# MY_DEMO_1602.net
KiCad netlist of a schematic drawn in Altium Designer
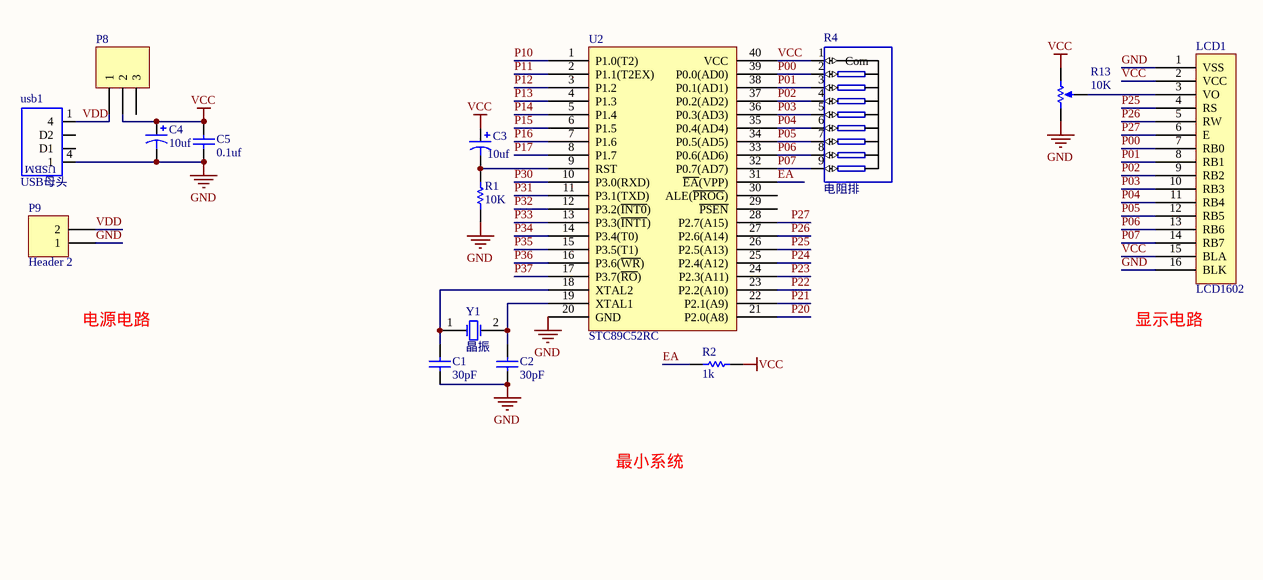
[diagram p0: MY_DEMO_1602.SchDoc]

(export (version "E")
  (design (tool "Eeschema 10.0.6"))
  (components
    (comp (ref "C1")
      (value "30pF")
      (footprint "RAD-0.1")
      (description "Capacitor")
      (fields (field (name "Comment") "瓷片电容") (field (name "PUBLISHER") "Altium Limited"))
      (libsource (lib "Miscellaneous Devices") (part "Cap"))
    )
    (comp (ref "C2")
      (value "30pF")
      (footprint "RAD-0.1")
      (description "Capacitor")
      (fields (field (name "Comment") "瓷片电容") (field (name "PUBLISHER") "Altium Limited"))
      (libsource (lib "Miscellaneous Devices") (part "Cap"))
    )
    (comp (ref "C3")
      (value "10uf")
      (footprint "10UF")
      (description "Polarized Capacitor (Radial)")
      (fields (field (name "Comment") "电解电容") (field (name "PUBLISHER") "Altium Limited"))
      (libsource (lib "Miscellaneous Devices") (part "Cap Pol1"))
    )
    (comp (ref "C4")
      (value "10uf")
      (footprint "10UF")
      (description "Polarized Capacitor (Radial)")
      (fields (field (name "Comment") "点解电容") (field (name "PUBLISHER") "Altium Limited"))
      (libsource (lib "Miscellaneous Devices") (part "Cap Pol1"))
    )
    (comp (ref "C5")
      (value "0.1uf")
      (footprint "CB1")
      (description "Capacitor")
      (fields (field (name "Comment") "瓷片电容") (field (name "PUBLISHER") "Altium Limited"))
      (libsource (lib "Miscellaneous Devices") (part "Cap"))
    )
    (comp (ref "LCD1") (value "LCD1602") (footprint "1602LCD") (libsource (lib "液晶") (part "LCD1602")))
    (comp (ref "P8")
      (value "Header 3")
      (footprint "HDR1X3")
      (description "Header, 3-Pin")
      (fields (field (name "PUBLISHER") "Altium Limited"))
      (libsource (lib "Miscellaneous Connectors") (part "Header 3"))
    )
    (comp (ref "P9")
      (value "Header 2")
      (footprint "HDR1X2")
      (description "Header, 2-Pin")
      (fields (field (name "PUBLISHER") "Altium Limited"))
      (libsource (lib "Miscellaneous Connectors") (part "Header 2"))
    )
    (comp (ref "R1")
      (value "10K")
      (footprint "电阻0.7-1.6")
      (description "Resistor")
      (fields (field (name "Comment") "电阻") (field (name "PUBLISHER") "Altium Limited"))
      (libsource (lib "Miscellaneous Devices") (part "Res1"))
    )
    (comp (ref "R2")
      (value "1k")
      (footprint "电阻0.7-1.6")
      (description "Resistor")
      (fields (field (name "Comment") "电阻") (field (name "PUBLISHER") "Altium Limited"))
      (libsource (lib "Miscellaneous Devices") (part "Res1"))
    )
    (comp (ref "R4") (value "电阻排") (footprint "插槽P9") (libsource (lib "电阻") (part "RES10")))
    (comp (ref "R13")
      (value "10K")
      (footprint "可调电阻5mm")
      (description "Potentiometer")
      (fields (field (name "Comment") "电位器RPot") (field (name "PUBLISHER") "Altium Limited"))
      (libsource (lib "Miscellaneous Devices") (part "RPot"))
    )
    (comp (ref "U2") (value "STC89C52RC") (footprint "DIP-40W") (libsource (lib "51单片机") (part "89C52")))
    (comp (ref "usb1") (value "USB母头") (footprint "A母USB") (libsource (lib "常用2") (part "USB")))
    (comp (ref "Y1")
      (value "晶振")
      (footprint "XTAL")
      (description "Crystal Oscillator")
      (fields (field (name "PUBLISHER") "Altium Limited"))
      (libsource (lib "Miscellaneous Devices") (part "XTAL"))
    )
  )
  (nets
    (net (code "1") (name "/EA") (class "Default")
      (node (ref "R2") (pin "2") (pinfunction "2_2") (pintype "passive"))
      (node (ref "U2") (pin "31") (pinfunction "~{EA}(VPP)_31") (pintype "passive"))
    )
    (net (code "2") (name "/P00") (class "Default")
      (node (ref "LCD1") (pin "7") (pinfunction "RB0_7") (pintype "passive"))
      (node (ref "R4") (pin "2") (pinfunction "2_2") (pintype "bidirectional"))
      (node (ref "U2") (pin "39") (pinfunction "P0.0(AD0)_39") (pintype "passive"))
    )
    (net (code "3") (name "/P01") (class "Default")
      (node (ref "LCD1") (pin "8") (pinfunction "RB1_8") (pintype "passive"))
      (node (ref "R4") (pin "3") (pinfunction "3_3") (pintype "bidirectional"))
      (node (ref "U2") (pin "38") (pinfunction "P0.1(AD1)_38") (pintype "passive"))
    )
    (net (code "4") (name "/P02") (class "Default")
      (node (ref "LCD1") (pin "9") (pinfunction "RB2_9") (pintype "passive"))
      (node (ref "R4") (pin "4") (pinfunction "4_4") (pintype "bidirectional"))
      (node (ref "U2") (pin "37") (pinfunction "P0.2(AD2)_37") (pintype "passive"))
    )
    (net (code "5") (name "/P03") (class "Default")
      (node (ref "LCD1") (pin "10") (pinfunction "RB3_10") (pintype "passive"))
      (node (ref "R4") (pin "5") (pinfunction "5_5") (pintype "bidirectional"))
      (node (ref "U2") (pin "36") (pinfunction "P0.3(AD3)_36") (pintype "passive"))
    )
    (net (code "6") (name "/P04") (class "Default")
      (node (ref "LCD1") (pin "11") (pinfunction "RB4_11") (pintype "passive"))
      (node (ref "R4") (pin "6") (pinfunction "6_6") (pintype "bidirectional"))
      (node (ref "U2") (pin "35") (pinfunction "P0.4(AD4)_35") (pintype "passive"))
    )
    (net (code "7") (name "/P05") (class "Default")
      (node (ref "LCD1") (pin "12") (pinfunction "RB5_12") (pintype "passive"))
      (node (ref "R4") (pin "7") (pinfunction "7_7") (pintype "bidirectional"))
      (node (ref "U2") (pin "34") (pinfunction "P0.5(AD5)_34") (pintype "passive"))
    )
    (net (code "8") (name "/P06") (class "Default")
      (node (ref "LCD1") (pin "13") (pinfunction "RB6_13") (pintype "passive"))
      (node (ref "R4") (pin "8") (pinfunction "8_8") (pintype "bidirectional"))
      (node (ref "U2") (pin "33") (pinfunction "P0.6(AD6)_33") (pintype "passive"))
    )
    (net (code "9") (name "/P07") (class "Default")
      (node (ref "LCD1") (pin "14") (pinfunction "RB7_14") (pintype "passive"))
      (node (ref "R4") (pin "9") (pinfunction "9_9") (pintype "bidirectional"))
      (node (ref "U2") (pin "32") (pinfunction "P0.7(AD7)_32") (pintype "passive"))
    )
    (net (code "10") (name "/P10") (class "Default")
      (node (ref "U2") (pin "1") (pinfunction "P1.0(T2)_1") (pintype "passive"))
    )
    (net (code "11") (name "/P11") (class "Default")
      (node (ref "U2") (pin "2") (pinfunction "P1.1(T2EX)_2") (pintype "passive"))
    )
    (net (code "12") (name "/P12") (class "Default")
      (node (ref "U2") (pin "3") (pinfunction "P1.2_3") (pintype "passive"))
    )
    (net (code "13") (name "/P13") (class "Default")
      (node (ref "U2") (pin "4") (pinfunction "P1.3_4") (pintype "passive"))
    )
    (net (code "14") (name "/P14") (class "Default")
      (node (ref "U2") (pin "5") (pinfunction "P1.4_5") (pintype "passive"))
    )
    (net (code "15") (name "/P15") (class "Default")
      (node (ref "U2") (pin "6") (pinfunction "P1.5_6") (pintype "passive"))
    )
    (net (code "16") (name "/P16") (class "Default")
      (node (ref "U2") (pin "7") (pinfunction "P1.6_7") (pintype "passive"))
    )
    (net (code "17") (name "/P17") (class "Default")
      (node (ref "U2") (pin "8") (pinfunction "P1.7_8") (pintype "passive"))
    )
    (net (code "18") (name "/P20") (class "Default")
      (node (ref "U2") (pin "21") (pinfunction "P2.0(A8)_21") (pintype "passive"))
    )
    (net (code "19") (name "/P21") (class "Default")
      (node (ref "U2") (pin "22") (pinfunction "P2.1(A9)_22") (pintype "passive"))
    )
    (net (code "20") (name "/P22") (class "Default")
      (node (ref "U2") (pin "23") (pinfunction "P2.2(A10)_23") (pintype "passive"))
    )
    (net (code "21") (name "/P23") (class "Default")
      (node (ref "U2") (pin "24") (pinfunction "P2.3(A11)_24") (pintype "passive"))
    )
    (net (code "22") (name "/P24") (class "Default")
      (node (ref "U2") (pin "25") (pinfunction "P2.4(A12)_25") (pintype "passive"))
    )
    (net (code "23") (name "/P25") (class "Default")
      (node (ref "LCD1") (pin "4") (pinfunction "RS_4") (pintype "passive"))
      (node (ref "U2") (pin "26") (pinfunction "P2.5(A13)_26") (pintype "passive"))
    )
    (net (code "24") (name "/P26") (class "Default")
      (node (ref "LCD1") (pin "5") (pinfunction "RW_5") (pintype "passive"))
      (node (ref "U2") (pin "27") (pinfunction "P2.6(A14)_27") (pintype "passive"))
    )
    (net (code "25") (name "/P27") (class "Default")
      (node (ref "LCD1") (pin "6") (pinfunction "E_6") (pintype "passive"))
      (node (ref "U2") (pin "28") (pinfunction "P2.7(A15)_28") (pintype "passive"))
    )
    (net (code "26") (name "/P30") (class "Default")
      (node (ref "U2") (pin "10") (pinfunction "P3.0(RXD)_10") (pintype "passive"))
    )
    (net (code "27") (name "/P31") (class "Default")
      (node (ref "U2") (pin "11") (pinfunction "P3.1(TXD)_11") (pintype "passive"))
    )
    (net (code "28") (name "/P32") (class "Default")
      (node (ref "U2") (pin "12") (pinfunction "P3.2(~{INT0})_12") (pintype "passive"))
    )
    (net (code "29") (name "/P33") (class "Default")
      (node (ref "U2") (pin "13") (pinfunction "P3.3(~{INT1})_13") (pintype "passive"))
    )
    (net (code "30") (name "/P34") (class "Default")
      (node (ref "U2") (pin "14") (pinfunction "P3.4(T0)_14") (pintype "passive"))
    )
    (net (code "31") (name "/P35") (class "Default")
      (node (ref "U2") (pin "15") (pinfunction "P3.5(T1)_15") (pintype "passive"))
    )
    (net (code "32") (name "/P36") (class "Default")
      (node (ref "U2") (pin "16") (pinfunction "P3.6(~{WR})_16") (pintype "passive"))
    )
    (net (code "33") (name "/P37") (class "Default")
      (node (ref "U2") (pin "17") (pinfunction "P3.7(~{RO})_17") (pintype "passive"))
    )
    (net (code "34") (name "/VDD") (class "Default")
      (node (ref "P8") (pin "1") (pinfunction "1_1") (pintype "passive"))
      (node (ref "P9") (pin "2") (pinfunction "2_2") (pintype "passive"))
      (node (ref "usb1") (pin "1") (pinfunction "4_1") (pintype "passive"))
    )
    (net (code "35") (name "GND") (class "Default")
      (node (ref "C1") (pin "1") (pinfunction "1_1") (pintype "passive"))
      (node (ref "C2") (pin "1") (pinfunction "1_1") (pintype "passive"))
      (node (ref "C4") (pin "2") (pinfunction "2_2") (pintype "passive"))
      (node (ref "C5") (pin "1") (pinfunction "1_1") (pintype "passive"))
      (node (ref "LCD1") (pin "1") (pinfunction "VSS_1") (pintype "passive"))
      (node (ref "LCD1") (pin "16") (pinfunction "BLK_16") (pintype "passive"))
      (node (ref "P9") (pin "1") (pinfunction "1_1") (pintype "passive"))
      (node (ref "R1") (pin "1") (pinfunction "1_1") (pintype "passive"))
      (node (ref "R13") (pin "1") (pinfunction "TOP_1") (pintype "passive"))
      (node (ref "U2") (pin "20") (pinfunction "GND_20") (pintype "passive"))
      (node (ref "usb1") (pin "4") (pinfunction "1_4") (pintype "passive"))
    )
    (net (code "36") (name "Net-(LCD1-VO)") (class "Default")
      (node (ref "LCD1") (pin "3") (pinfunction "VO_3") (pintype "passive"))
      (node (ref "R13") (pin "3") (pinfunction "TAP_3") (pintype "passive"))
    )
    (net (code "37") (name "Net-(U2-RST)") (class "Default")
      (node (ref "C3") (pin "2") (pinfunction "2_2") (pintype "passive"))
      (node (ref "R1") (pin "2") (pinfunction "2_2") (pintype "passive"))
      (node (ref "U2") (pin "9") (pinfunction "RST_9") (pintype "passive"))
    )
    (net (code "38") (name "Net-(U2-XTAL1)") (class "Default")
      (node (ref "C2") (pin "2") (pinfunction "2_2") (pintype "passive"))
      (node (ref "U2") (pin "19") (pinfunction "XTAL1_19") (pintype "passive"))
      (node (ref "Y1") (pin "2") (pinfunction "OSC2_2") (pintype "passive"))
    )
    (net (code "39") (name "Net-(U2-XTAL2)") (class "Default")
      (node (ref "C1") (pin "2") (pinfunction "2_2") (pintype "passive"))
      (node (ref "U2") (pin "18") (pinfunction "XTAL2_18") (pintype "passive"))
      (node (ref "Y1") (pin "1") (pinfunction "OSC1_1") (pintype "passive"))
    )
    (net (code "40") (name "VCC") (class "Default")
      (node (ref "C3") (pin "1") (pinfunction "1_1") (pintype "passive"))
      (node (ref "C4") (pin "1") (pinfunction "1_1") (pintype "passive"))
      (node (ref "C5") (pin "2") (pinfunction "2_2") (pintype "passive"))
      (node (ref "LCD1") (pin "15") (pinfunction "BLA_15") (pintype "passive"))
      (node (ref "LCD1") (pin "2") (pinfunction "VCC_2") (pintype "passive"))
      (node (ref "P8") (pin "2") (pinfunction "2_2") (pintype "passive"))
      (node (ref "R13") (pin "2") (pinfunction "BOT_2") (pintype "passive"))
      (node (ref "R2") (pin "1") (pinfunction "1_1") (pintype "passive"))
      (node (ref "R4") (pin "1") (pinfunction "Com_1") (pintype "bidirectional"))
      (node (ref "U2") (pin "40") (pinfunction "VCC_40") (pintype "passive"))
    )
    (net (code "41") (name "unconnected-(P8-Pad3)") (class "Default")
      (node (ref "P8") (pin "3") (pinfunction "3_3") (pintype "passive"))
    )
    (net (code "42") (name "unconnected-(U2-ALE(~{PROG})-Pad30)") (class "Default")
      (node (ref "U2") (pin "30") (pinfunction "ALE(~{PROG})_30") (pintype "passive"))
    )
    (net (code "43") (name "unconnected-(U2-~{PSEN}-Pad29)") (class "Default")
      (node (ref "U2") (pin "29") (pinfunction "~{PSEN}_29") (pintype "passive"))
    )
    (net (code "44") (name "unconnected-(usb1-PadD1)") (class "Default")
      (node (ref "usb1") (pin "D1") (pinfunction "D1_D1") (pintype "passive"))
    )
    (net (code "45") (name "unconnected-(usb1-PadD2)") (class "Default")
      (node (ref "usb1") (pin "D2") (pinfunction "D2_D2") (pintype "passive"))
    )
  )
)
